# AD9834.net
KiCad netlist of a schematic drawn in Altium Designer
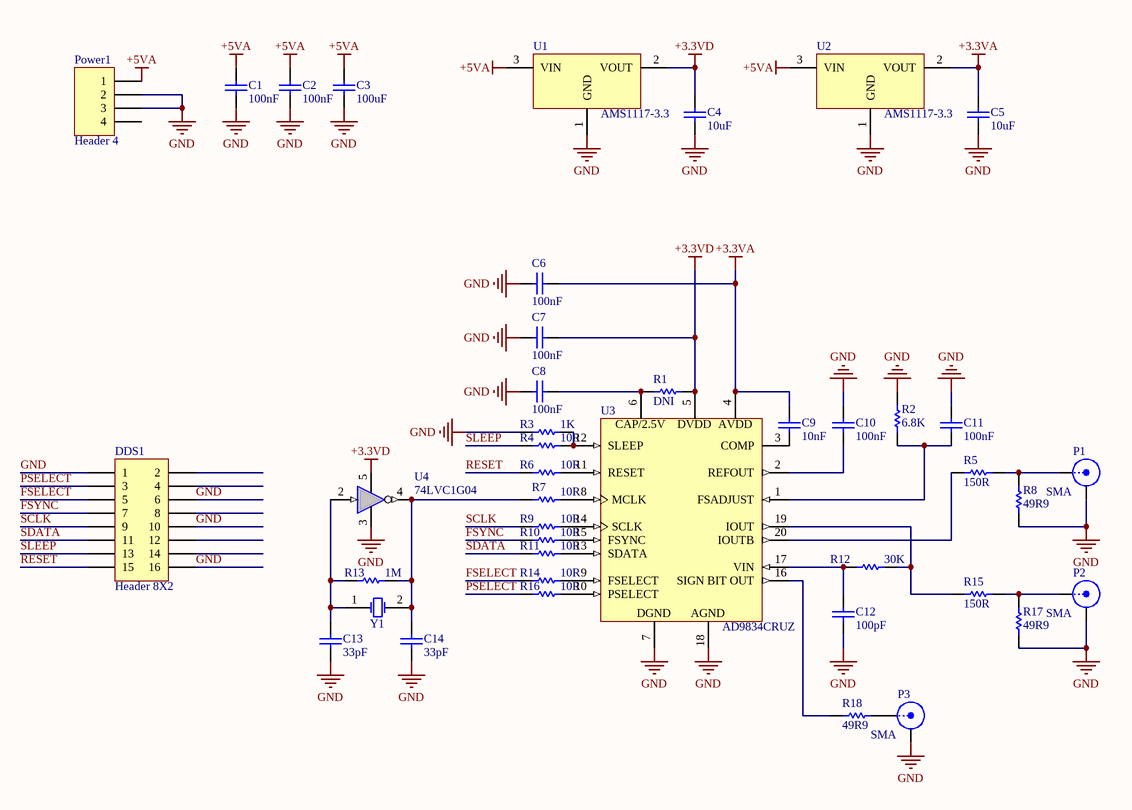
[diagram p0: AD9834.SchDoc]

(export (version "E")
  (design (tool "Eeschema 10.0.6"))
  (components
    (comp (ref "C1")
      (value "100nF")
      (footprint "CAPC0603(1608)55_M")
      (libsource (lib "Slivy's Library") (part "CAP"))
    )
    (comp (ref "C2")
      (value "100nF")
      (footprint "CAPC0603(1608)55_M")
      (libsource (lib "Slivy's Library") (part "CAP"))
    )
    (comp (ref "C3") (value "100uF") (footprint "CAPC3225") (libsource (lib "Slivy's Library") (part "CAP")))
    (comp (ref "C4")
      (value "10uF")
      (footprint "CAPC0805(2012)75_M")
      (libsource (lib "Slivy's Library") (part "CAP"))
    )
    (comp (ref "C5")
      (value "10uF")
      (footprint "CAPC0805(2012)75_M")
      (libsource (lib "Slivy's Library") (part "CAP"))
    )
    (comp (ref "C6")
      (value "100nF")
      (footprint "CAPC0603(1608)55_M")
      (libsource (lib "Slivy's Library") (part "CAP"))
    )
    (comp (ref "C7")
      (value "100nF")
      (footprint "CAPC0603(1608)55_M")
      (libsource (lib "Slivy's Library") (part "CAP"))
    )
    (comp (ref "C8")
      (value "100nF")
      (footprint "CAPC0603(1608)55_M")
      (libsource (lib "Slivy's Library") (part "CAP"))
    )
    (comp (ref "C9")
      (value "10nF")
      (footprint "CAPC0603(1608)55_M")
      (libsource (lib "Slivy's Library") (part "CAP"))
    )
    (comp (ref "C10")
      (value "100nF")
      (footprint "CAPC0603(1608)55_M")
      (libsource (lib "Slivy's Library") (part "CAP"))
    )
    (comp (ref "C11")
      (value "100nF")
      (footprint "CAPC0603(1608)55_M")
      (libsource (lib "Slivy's Library") (part "CAP"))
    )
    (comp (ref "C12")
      (value "100pF")
      (footprint "CAPC0603(1608)55_M")
      (libsource (lib "Slivy's Library") (part "CAP"))
    )
    (comp (ref "C13")
      (value "33pF")
      (footprint "CAPC0603(1608)55_M")
      (libsource (lib "Slivy's Library") (part "CAP"))
    )
    (comp (ref "C14")
      (value "33pF")
      (footprint "CAPC0603(1608)55_M")
      (libsource (lib "Slivy's Library") (part "CAP"))
    )
    (comp (ref "DDS1")
      (value "Header 8X2")
      (footprint "Header8X2")
      (description "Header, 8-Pin, Dual row")
      (fields (field (name "PUBLISHER") "Altium Limited"))
      (libsource (lib "Miscellaneous Connectors") (part "Header 8X2"))
    )
    (comp (ref "P1")
      (value "SMA")
      (footprint "SMA-V")
      (fields (field (name "PUBLISHER") "Altium Limited"))
      (libsource (lib "Slivy's Library") (part "SMA"))
    )
    (comp (ref "P2")
      (value "SMA")
      (footprint "SMA-V")
      (fields (field (name "PUBLISHER") "Altium Limited"))
      (libsource (lib "Slivy's Library") (part "SMA"))
    )
    (comp (ref "P3")
      (value "SMA")
      (footprint "SMA-V")
      (fields (field (name "PUBLISHER") "Altium Limited"))
      (libsource (lib "Slivy's Library") (part "SMA"))
    )
    (comp (ref "Power1")
      (value "Header 4")
      (footprint "3.96-4")
      (description "Header, 4-Pin")
      (fields (field (name "MANUFACTURER") "Generic Components"))
      (libsource (lib "Integrated_Library1") (part "Header 4"))
    )
    (comp (ref "R1")
      (value "DNI")
      (footprint "RESC0603(1608)_M")
      (libsource (lib "Slivy's Library") (part "RES"))
    )
    (comp (ref "R2")
      (value "6.8K")
      (footprint "RESC0603(1608)_M")
      (libsource (lib "Slivy's Library") (part "RES"))
    )
    (comp (ref "R3")
      (value "1K")
      (footprint "RESC0603(1608)_M")
      (libsource (lib "Slivy's Library") (part "RES"))
    )
    (comp (ref "R4")
      (value "10R")
      (footprint "RESC0603(1608)_M")
      (libsource (lib "Slivy's Library") (part "RES"))
    )
    (comp (ref "R5")
      (value "150R")
      (footprint "RESC0603(1608)_M")
      (libsource (lib "Slivy's Library") (part "RES"))
    )
    (comp (ref "R6")
      (value "10R")
      (footprint "RESC0603(1608)_M")
      (libsource (lib "Slivy's Library") (part "RES"))
    )
    (comp (ref "R7")
      (value "10R")
      (footprint "RESC0603(1608)_M")
      (libsource (lib "Slivy's Library") (part "RES"))
    )
    (comp (ref "R8")
      (value "49R9")
      (footprint "RESC0603(1608)_M")
      (libsource (lib "Slivy's Library") (part "RES"))
    )
    (comp (ref "R9")
      (value "10R")
      (footprint "RESC0603(1608)_M")
      (libsource (lib "Slivy's Library") (part "RES"))
    )
    (comp (ref "R10")
      (value "10R")
      (footprint "RESC0603(1608)_M")
      (libsource (lib "Slivy's Library") (part "RES"))
    )
    (comp (ref "R11")
      (value "10R")
      (footprint "RESC0603(1608)_M")
      (libsource (lib "Slivy's Library") (part "RES"))
    )
    (comp (ref "R12")
      (value "30K")
      (footprint "RESC0603(1608)_M")
      (libsource (lib "Slivy's Library") (part "RES"))
    )
    (comp (ref "R13")
      (value "1M")
      (footprint "RESC0603(1608)_M")
      (libsource (lib "Slivy's Library") (part "RES"))
    )
    (comp (ref "R14")
      (value "10R")
      (footprint "RESC0603(1608)_M")
      (libsource (lib "Slivy's Library") (part "RES"))
    )
    (comp (ref "R15")
      (value "150R")
      (footprint "RESC0603(1608)_M")
      (libsource (lib "Slivy's Library") (part "RES"))
    )
    (comp (ref "R16")
      (value "10R")
      (footprint "RESC0603(1608)_M")
      (libsource (lib "Slivy's Library") (part "RES"))
    )
    (comp (ref "R17")
      (value "49R9")
      (footprint "RESC0603(1608)_M")
      (libsource (lib "Slivy's Library") (part "RES"))
    )
    (comp (ref "R18")
      (value "49R9")
      (footprint "RESC0603(1608)_M")
      (libsource (lib "Slivy's Library") (part "RES"))
    )
    (comp (ref "U1")
      (value "AMS1117-3.3")
      (footprint "SOT-223_M")
      (libsource (lib "Slivy's Library") (part "AMS1117"))
    )
    (comp (ref "U2")
      (value "AMS1117-3.3")
      (footprint "SOT-223_M")
      (libsource (lib "Slivy's Library") (part "AMS1117"))
    )
    (comp (ref "U3")
      (value "AD9834CRUZ")
      (footprint "RU-20")
      (libsource (lib "Slivy's Library") (part "AD9834CRUZ"))
    )
    (comp (ref "U4")
      (value "74LVC1G04")
      (footprint "SOT753")
      (libsource (lib "Slivy's Library") (part "74LVC1G04"))
    )
    (comp (ref "Y1")
      (value "XTAL")
      (footprint "HC-49S")
      (description "Crystal Oscillator")
      (fields (field (name "PUBLISHER") "Altium Limited"))
      (libsource (lib "Slivy's Library") (part "XTAL"))
    )
  )
  (nets
    (net (code "1") (name "+3.3VA") (class "Default")
      (node (ref "C5") (pin "2") (pinfunction "2_2") (pintype "passive"))
      (node (ref "C6") (pin "2") (pinfunction "2_2") (pintype "passive"))
      (node (ref "C9") (pin "2") (pinfunction "2_2") (pintype "passive"))
      (node (ref "U2") (pin "2") (pinfunction "VOUT_2") (pintype "power_in"))
      (node (ref "U3") (pin "4") (pinfunction "AVDD_4") (pintype "power_in"))
    )
    (net (code "2") (name "+3.3VD") (class "Default")
      (node (ref "C4") (pin "2") (pinfunction "2_2") (pintype "passive"))
      (node (ref "C7") (pin "2") (pinfunction "2_2") (pintype "passive"))
      (node (ref "R1") (pin "1") (pinfunction "1_1") (pintype "passive"))
      (node (ref "U1") (pin "2") (pinfunction "VOUT_2") (pintype "power_in"))
      (node (ref "U3") (pin "5") (pinfunction "DVDD_5") (pintype "power_in"))
      (node (ref "U4") (pin "5") (pinfunction "VCC_5") (pintype "power_in"))
    )
    (net (code "3") (name "+5VA") (class "Default")
      (node (ref "C1") (pin "2") (pinfunction "2_2") (pintype "passive"))
      (node (ref "C2") (pin "2") (pinfunction "2_2") (pintype "passive"))
      (node (ref "C3") (pin "2") (pinfunction "2_2") (pintype "passive"))
      (node (ref "Power1") (pin "1") (pinfunction "1_1") (pintype "passive"))
      (node (ref "U1") (pin "3") (pinfunction "VIN_3") (pintype "power_in"))
      (node (ref "U2") (pin "3") (pinfunction "VIN_3") (pintype "power_in"))
    )
    (net (code "4") (name "/FSELECT") (class "Default")
      (node (ref "DDS1") (pin "5") (pinfunction "5_5") (pintype "passive"))
      (node (ref "R14") (pin "2") (pinfunction "2_2") (pintype "passive"))
    )
    (net (code "5") (name "/FSYNC") (class "Default")
      (node (ref "DDS1") (pin "7") (pinfunction "7_7") (pintype "passive"))
      (node (ref "R10") (pin "2") (pinfunction "2_2") (pintype "passive"))
    )
    (net (code "6") (name "/PSELECT") (class "Default")
      (node (ref "DDS1") (pin "3") (pinfunction "3_3") (pintype "passive"))
      (node (ref "R16") (pin "2") (pinfunction "2_2") (pintype "passive"))
    )
    (net (code "7") (name "/RESET") (class "Default")
      (node (ref "DDS1") (pin "15") (pinfunction "15_15") (pintype "passive"))
      (node (ref "R6") (pin "2") (pinfunction "2_2") (pintype "passive"))
    )
    (net (code "8") (name "/SCLK") (class "Default")
      (node (ref "DDS1") (pin "9") (pinfunction "9_9") (pintype "passive"))
      (node (ref "R9") (pin "2") (pinfunction "2_2") (pintype "passive"))
    )
    (net (code "9") (name "/SDATA") (class "Default")
      (node (ref "DDS1") (pin "11") (pinfunction "11_11") (pintype "passive"))
      (node (ref "R11") (pin "2") (pinfunction "2_2") (pintype "passive"))
    )
    (net (code "10") (name "/SLEEP") (class "Default")
      (node (ref "DDS1") (pin "13") (pinfunction "13_13") (pintype "passive"))
      (node (ref "R4") (pin "2") (pinfunction "2_2") (pintype "passive"))
    )
    (net (code "11") (name "GND") (class "Default")
      (node (ref "C1") (pin "1") (pinfunction "1_1") (pintype "passive"))
      (node (ref "C10") (pin "2") (pinfunction "2_2") (pintype "passive"))
      (node (ref "C11") (pin "2") (pinfunction "2_2") (pintype "passive"))
      (node (ref "C12") (pin "1") (pinfunction "1_1") (pintype "passive"))
      (node (ref "C13") (pin "1") (pinfunction "1_1") (pintype "passive"))
      (node (ref "C14") (pin "1") (pinfunction "1_1") (pintype "passive"))
      (node (ref "C2") (pin "1") (pinfunction "1_1") (pintype "passive"))
      (node (ref "C3") (pin "1") (pinfunction "1_1") (pintype "passive"))
      (node (ref "C4") (pin "1") (pinfunction "1_1") (pintype "passive"))
      (node (ref "C5") (pin "1") (pinfunction "1_1") (pintype "passive"))
      (node (ref "C6") (pin "1") (pinfunction "1_1") (pintype "passive"))
      (node (ref "C7") (pin "1") (pinfunction "1_1") (pintype "passive"))
      (node (ref "C8") (pin "1") (pinfunction "1_1") (pintype "passive"))
      (node (ref "DDS1") (pin "1") (pinfunction "1_1") (pintype "passive"))
      (node (ref "DDS1") (pin "10") (pinfunction "10_10") (pintype "passive"))
      (node (ref "DDS1") (pin "16") (pinfunction "16_16") (pintype "passive"))
      (node (ref "DDS1") (pin "6") (pinfunction "6_6") (pintype "passive"))
      (node (ref "P1") (pin "2") (pinfunction "Y_2") (pintype "passive"))
      (node (ref "P2") (pin "2") (pinfunction "Y_2") (pintype "passive"))
      (node (ref "P3") (pin "2") (pinfunction "Y_2") (pintype "passive"))
      (node (ref "Power1") (pin "2") (pinfunction "2_2") (pintype "passive"))
      (node (ref "Power1") (pin "3") (pinfunction "3_3") (pintype "passive"))
      (node (ref "R17") (pin "2") (pinfunction "2_2") (pintype "passive"))
      (node (ref "R2") (pin "1") (pinfunction "1_1") (pintype "passive"))
      (node (ref "R3") (pin "2") (pinfunction "2_2") (pintype "passive"))
      (node (ref "R8") (pin "2") (pinfunction "2_2") (pintype "passive"))
      (node (ref "U1") (pin "1") (pinfunction "GND_1") (pintype "power_in"))
      (node (ref "U2") (pin "1") (pinfunction "GND_1") (pintype "power_in"))
      (node (ref "U3") (pin "18") (pinfunction "AGND_18") (pintype "power_in"))
      (node (ref "U3") (pin "7") (pinfunction "DGND_7") (pintype "power_in"))
      (node (ref "U4") (pin "3") (pinfunction "GND_3") (pintype "power_in"))
    )
    (net (code "12") (name "Net-(P1-X)") (class "Default")
      (node (ref "P1") (pin "1") (pinfunction "X_1") (pintype "passive"))
      (node (ref "R5") (pin "1") (pinfunction "1_1") (pintype "passive"))
      (node (ref "R8") (pin "1") (pinfunction "1_1") (pintype "passive"))
    )
    (net (code "13") (name "Net-(P2-X)") (class "Default")
      (node (ref "P2") (pin "1") (pinfunction "X_1") (pintype "passive"))
      (node (ref "R15") (pin "1") (pinfunction "1_1") (pintype "passive"))
      (node (ref "R17") (pin "1") (pinfunction "1_1") (pintype "passive"))
    )
    (net (code "14") (name "Net-(P3-X)") (class "Default")
      (node (ref "P3") (pin "1") (pinfunction "X_1") (pintype "passive"))
      (node (ref "R18") (pin "1") (pinfunction "1_1") (pintype "passive"))
    )
    (net (code "15") (name "Net-(U3-CAP{slash}2.5V)") (class "Default")
      (node (ref "C8") (pin "2") (pinfunction "2_2") (pintype "passive"))
      (node (ref "R1") (pin "2") (pinfunction "2_2") (pintype "passive"))
      (node (ref "U3") (pin "6") (pinfunction "CAP/2.5V_6") (pintype "power_in"))
    )
    (net (code "16") (name "Net-(U3-COMP)") (class "Default")
      (node (ref "C9") (pin "1") (pinfunction "1_1") (pintype "passive"))
      (node (ref "U3") (pin "3") (pinfunction "COMP_3") (pintype "passive"))
    )
    (net (code "17") (name "Net-(U3-FSADJUST)") (class "Default")
      (node (ref "C11") (pin "1") (pinfunction "1_1") (pintype "passive"))
      (node (ref "R2") (pin "2") (pinfunction "2_2") (pintype "passive"))
      (node (ref "U3") (pin "1") (pinfunction "FSADJUST_1") (pintype "input"))
    )
    (net (code "18") (name "Net-(U3-FSELECT)") (class "Default")
      (node (ref "R14") (pin "1") (pinfunction "1_1") (pintype "passive"))
      (node (ref "U3") (pin "9") (pinfunction "FSELECT_9") (pintype "input"))
    )
    (net (code "19") (name "Net-(U3-FSYNC)") (class "Default")
      (node (ref "R10") (pin "1") (pinfunction "1_1") (pintype "passive"))
      (node (ref "U3") (pin "15") (pinfunction "FSYNC_15") (pintype "input"))
    )
    (net (code "20") (name "Net-(U3-IOUT)") (class "Default")
      (node (ref "R12") (pin "1") (pinfunction "1_1") (pintype "passive"))
      (node (ref "R15") (pin "2") (pinfunction "2_2") (pintype "passive"))
      (node (ref "U3") (pin "19") (pinfunction "IOUT_19") (pintype "output"))
    )
    (net (code "21") (name "Net-(U3-IOUTB)") (class "Default")
      (node (ref "R5") (pin "2") (pinfunction "2_2") (pintype "passive"))
      (node (ref "U3") (pin "20") (pinfunction "IOUTB_20") (pintype "output"))
    )
    (net (code "22") (name "Net-(U3-MCLK)") (class "Default")
      (node (ref "R7") (pin "1") (pinfunction "1_1") (pintype "passive"))
      (node (ref "U3") (pin "8") (pinfunction "MCLK_8") (pintype "input"))
    )
    (net (code "23") (name "Net-(U3-PSELECT)") (class "Default")
      (node (ref "R16") (pin "1") (pinfunction "1_1") (pintype "passive"))
      (node (ref "U3") (pin "10") (pinfunction "PSELECT_10") (pintype "input"))
    )
    (net (code "24") (name "Net-(U3-REFOUT)") (class "Default")
      (node (ref "C10") (pin "1") (pinfunction "1_1") (pintype "passive"))
      (node (ref "U3") (pin "2") (pinfunction "REFOUT_2") (pintype "output"))
    )
    (net (code "25") (name "Net-(U3-RESET)") (class "Default")
      (node (ref "R6") (pin "1") (pinfunction "1_1") (pintype "passive"))
      (node (ref "U3") (pin "11") (pinfunction "RESET_11") (pintype "input"))
    )
    (net (code "26") (name "Net-(U3-SCLK)") (class "Default")
      (node (ref "R9") (pin "1") (pinfunction "1_1") (pintype "passive"))
      (node (ref "U3") (pin "14") (pinfunction "SCLK_14") (pintype "input"))
    )
    (net (code "27") (name "Net-(U3-SDATA)") (class "Default")
      (node (ref "R11") (pin "1") (pinfunction "1_1") (pintype "passive"))
      (node (ref "U3") (pin "13") (pinfunction "SDATA_13") (pintype "input"))
    )
    (net (code "28") (name "Net-(U3-SIGN_BIT_OUT)") (class "Default")
      (node (ref "R18") (pin "2") (pinfunction "2_2") (pintype "passive"))
      (node (ref "U3") (pin "16") (pinfunction "SIGN_BIT_OUT_16") (pintype "output"))
    )
    (net (code "29") (name "Net-(U3-SLEEP)") (class "Default")
      (node (ref "R3") (pin "1") (pinfunction "1_1") (pintype "passive"))
      (node (ref "R4") (pin "1") (pinfunction "1_1") (pintype "passive"))
      (node (ref "U3") (pin "12") (pinfunction "SLEEP_12") (pintype "input"))
    )
    (net (code "30") (name "Net-(U3-VIN)") (class "Default")
      (node (ref "C12") (pin "2") (pinfunction "2_2") (pintype "passive"))
      (node (ref "R12") (pin "2") (pinfunction "2_2") (pintype "passive"))
      (node (ref "U3") (pin "17") (pinfunction "VIN_17") (pintype "input"))
    )
    (net (code "31") (name "Net-(U4-A)") (class "Default")
      (node (ref "C13") (pin "2") (pinfunction "2_2") (pintype "passive"))
      (node (ref "R13") (pin "2") (pinfunction "2_2") (pintype "passive"))
      (node (ref "U4") (pin "2") (pinfunction "A_2") (pintype "input"))
      (node (ref "Y1") (pin "1") (pinfunction "OSC1_1") (pintype "passive"))
    )
    (net (code "32") (name "Net-(U4-Y)") (class "Default")
      (node (ref "C14") (pin "2") (pinfunction "2_2") (pintype "passive"))
      (node (ref "R13") (pin "1") (pinfunction "1_1") (pintype "passive"))
      (node (ref "R7") (pin "2") (pinfunction "2_2") (pintype "passive"))
      (node (ref "U4") (pin "4") (pinfunction "Y_4") (pintype "output"))
      (node (ref "Y1") (pin "2") (pinfunction "OSC2_2") (pintype "passive"))
    )
    (net (code "33") (name "unconnected-(DDS1-Pad2)") (class "Default")
      (node (ref "DDS1") (pin "2") (pinfunction "2_2") (pintype "passive"))
    )
    (net (code "34") (name "unconnected-(DDS1-Pad4)") (class "Default")
      (node (ref "DDS1") (pin "4") (pinfunction "4_4") (pintype "passive"))
    )
    (net (code "35") (name "unconnected-(DDS1-Pad8)") (class "Default")
      (node (ref "DDS1") (pin "8") (pinfunction "8_8") (pintype "passive"))
    )
    (net (code "36") (name "unconnected-(DDS1-Pad12)") (class "Default")
      (node (ref "DDS1") (pin "12") (pinfunction "12_12") (pintype "passive"))
    )
    (net (code "37") (name "unconnected-(DDS1-Pad14)") (class "Default")
      (node (ref "DDS1") (pin "14") (pinfunction "14_14") (pintype "passive"))
    )
    (net (code "38") (name "unconnected-(Power1-Pad4)") (class "Default")
      (node (ref "Power1") (pin "4") (pinfunction "4_4") (pintype "passive"))
    )
  )
)
